# ESP-12E_Dev_Board_with_level_shifter.net
KiCad netlist of a schematic drawn in EAGLE
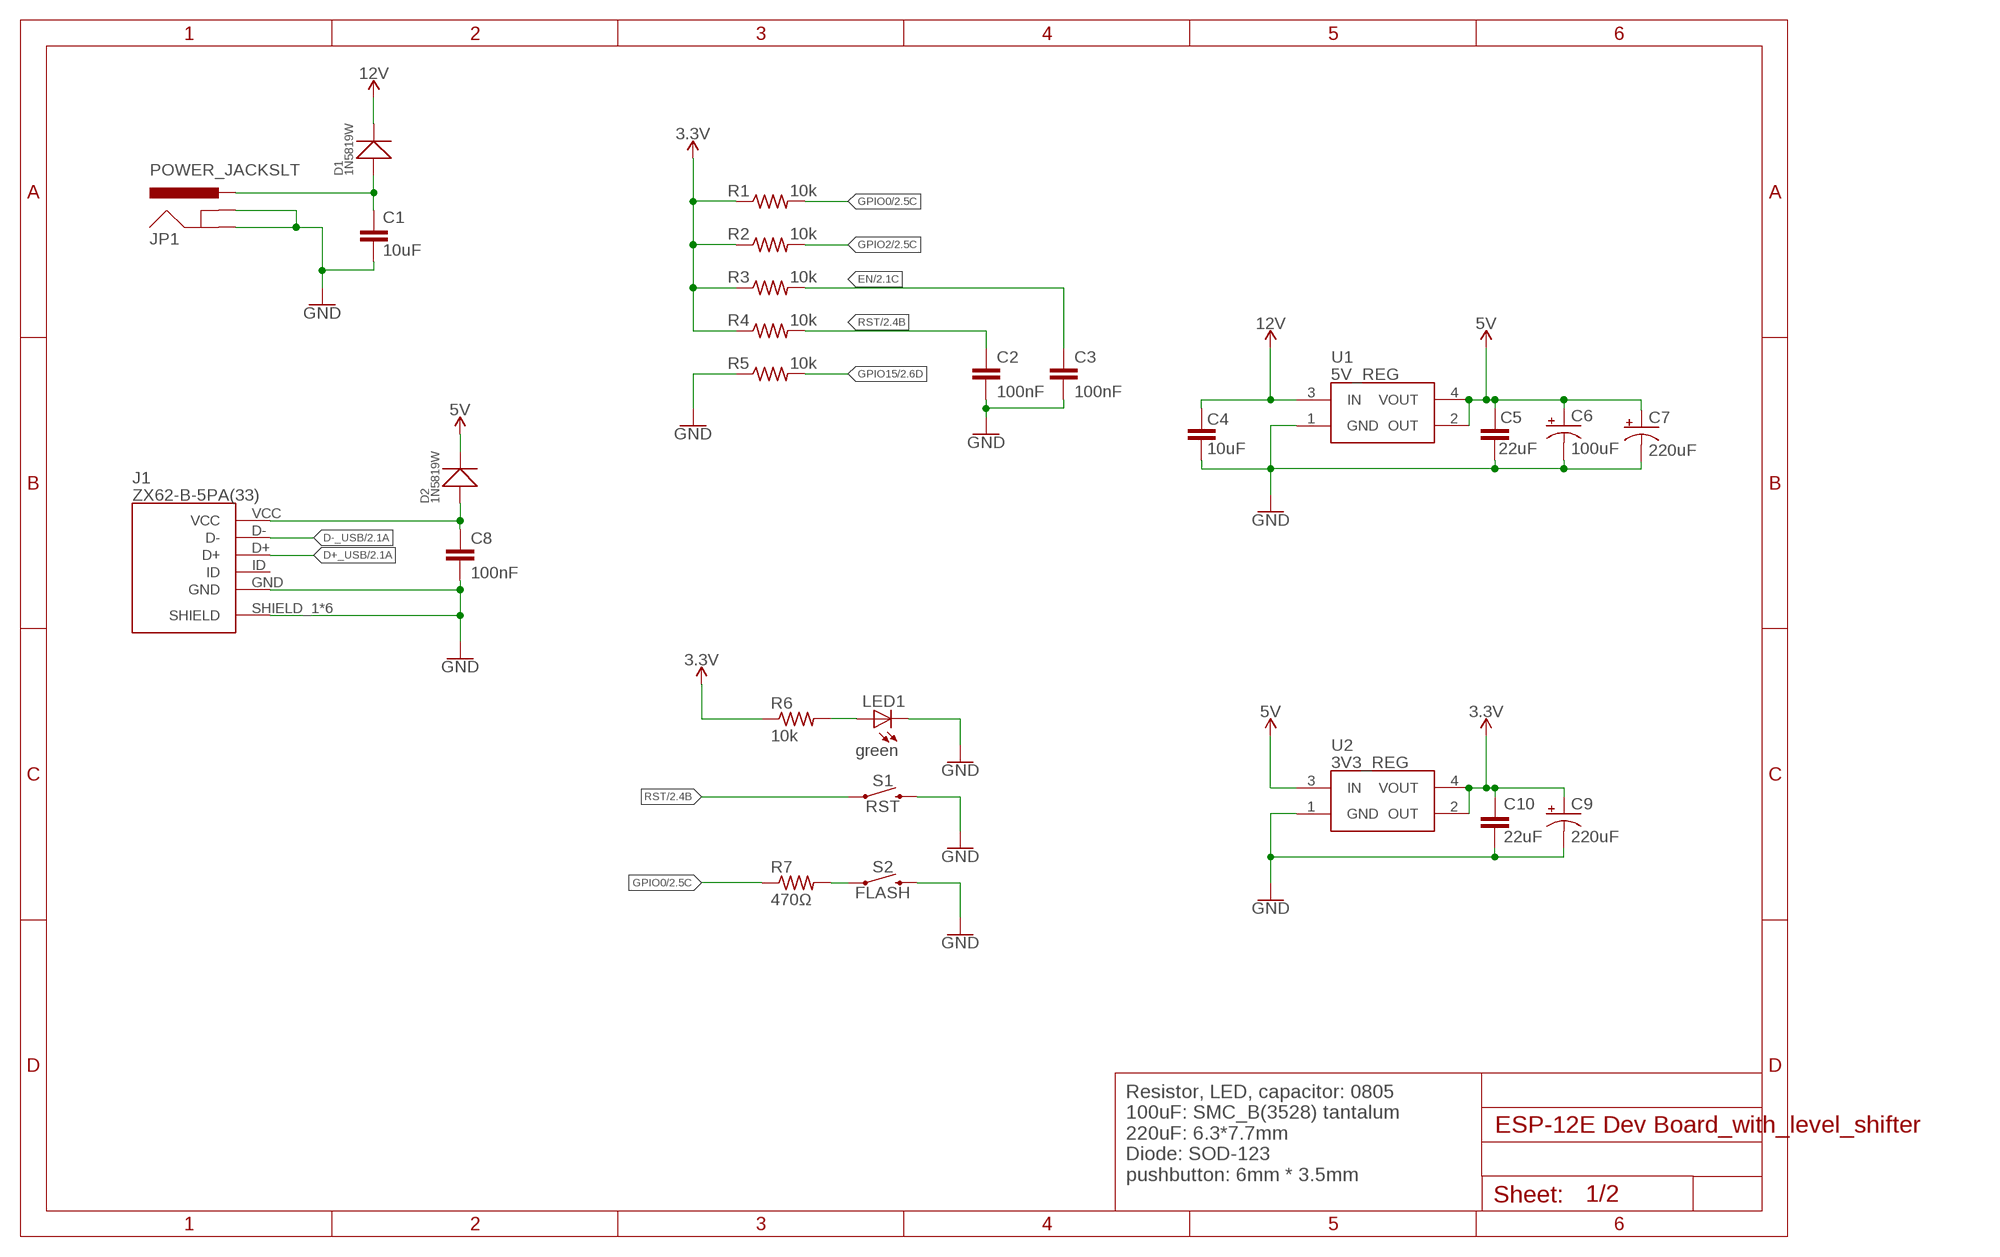
[diagram p0: schematic, sheet 1]
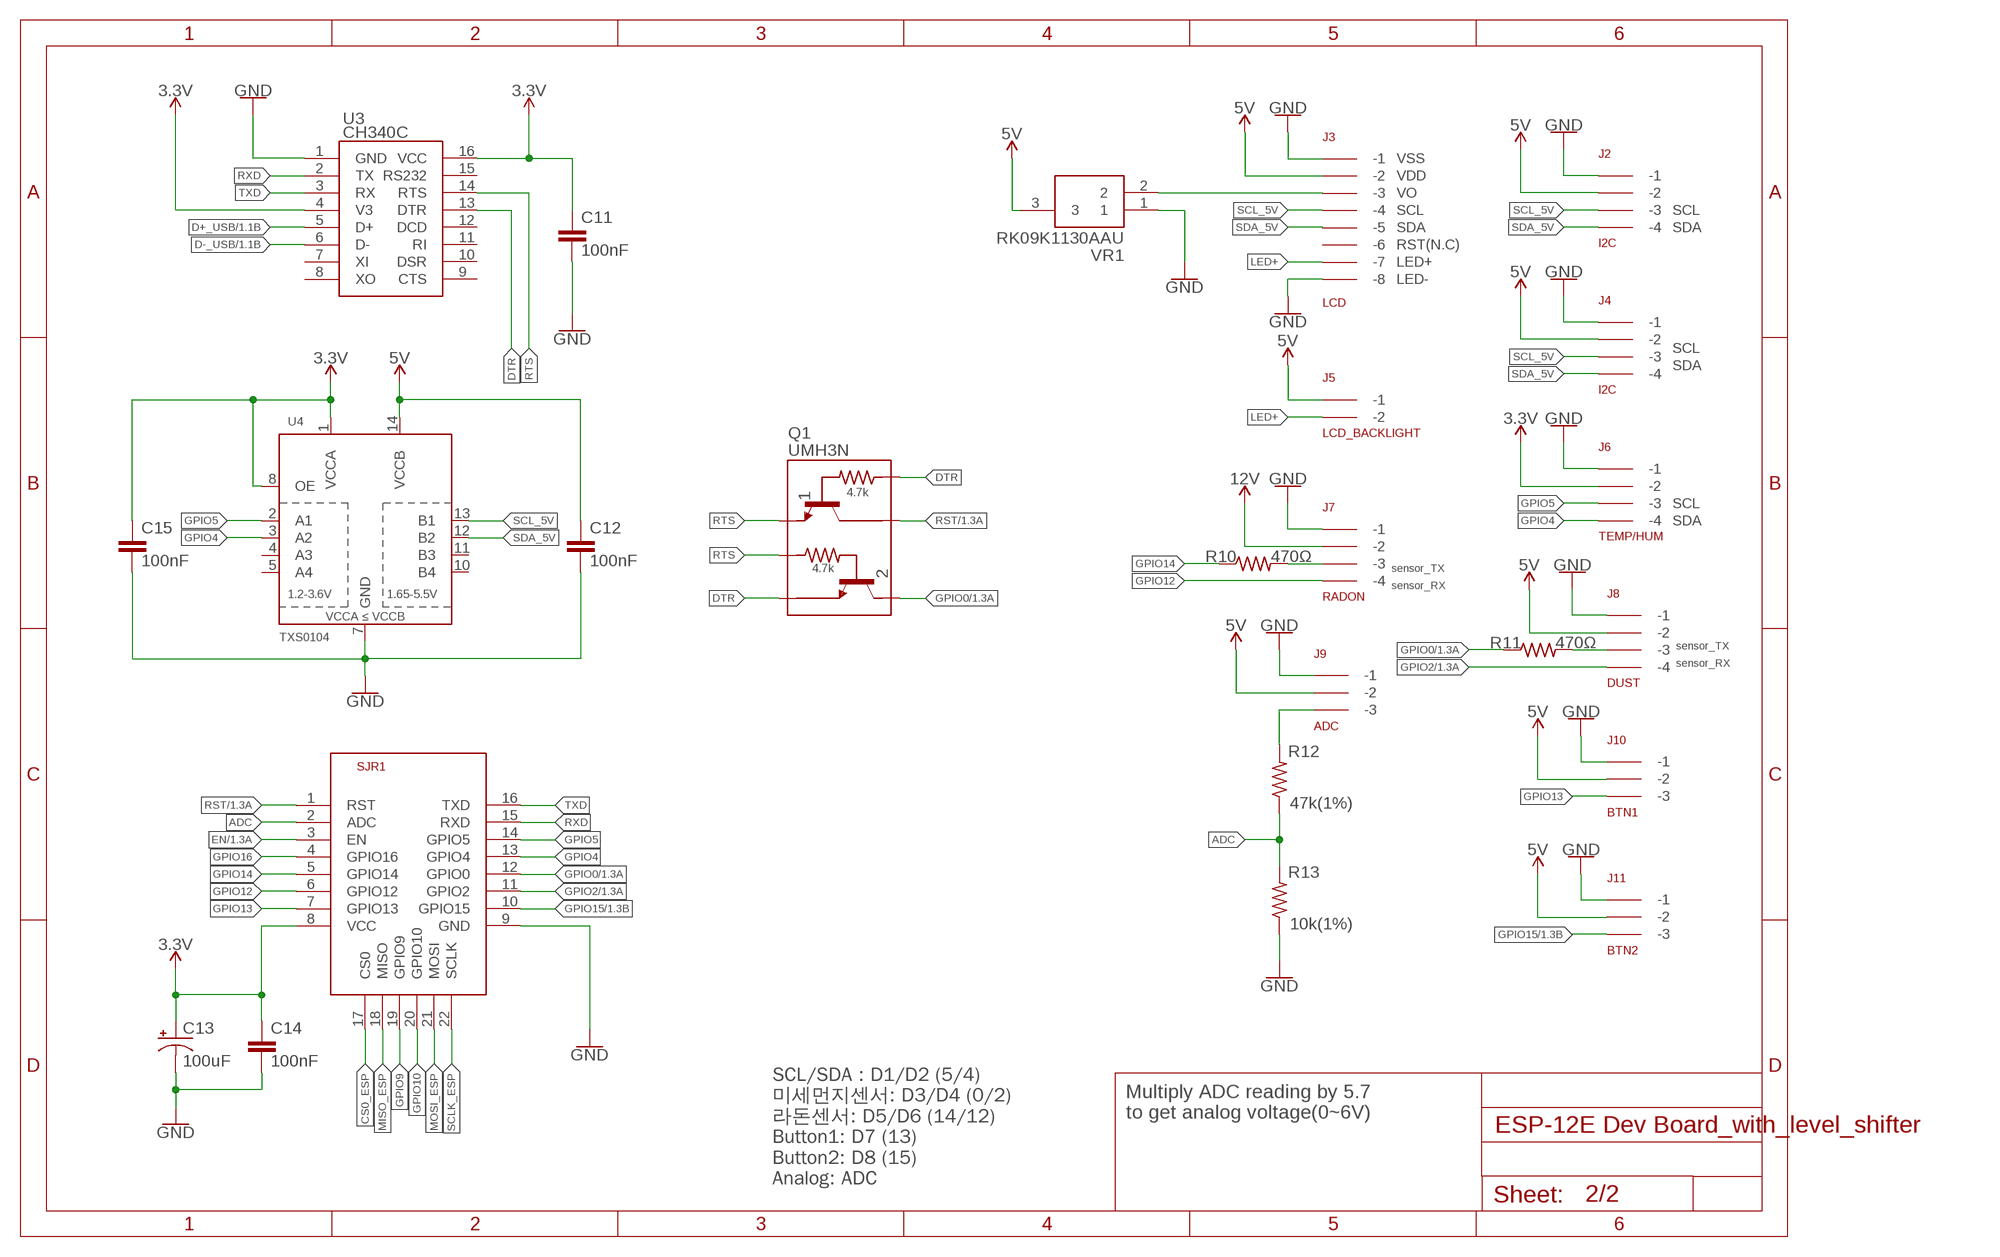
[diagram p1: schematic, sheet 2]

(export (version "E")
  (design (tool "Eeschema 10.0.6"))
  (components
    (comp (ref "C11")
      (value "100nF")
      (footprint "eagle-import:C0805")
      (libsource (lib "eagle-import") (part "C-EUC0805"))
    )
    (comp (ref "C12")
      (value "100nF")
      (footprint "eagle-import:C0805")
      (libsource (lib "eagle-import") (part "C-EUC0805"))
    )
    (comp (ref "C13")
      (value "100uF")
      (footprint "eagle-import:SMC_B")
      (libsource (lib "eagle-import") (part "CPOL-USSMCB"))
    )
    (comp (ref "C14")
      (value "100nF")
      (footprint "eagle-import:C0805")
      (libsource (lib "eagle-import") (part "C-EUC0805"))
    )
    (comp (ref "C15")
      (value "100nF")
      (footprint "eagle-import:C0805")
      (libsource (lib "eagle-import") (part "C-EUC0805"))
    )
    (comp (ref "J2")
      (value "I2C")
      (footprint "eagle-import:5267-4")
      (libsource (lib "eagle-import") (part "5267-4"))
    )
    (comp (ref "J3")
      (value "LCD")
      (footprint "eagle-import:5267-8")
      (libsource (lib "eagle-import") (part "5267-8"))
    )
    (comp (ref "J4")
      (value "I2C")
      (footprint "eagle-import:5267-4")
      (libsource (lib "eagle-import") (part "5267-4"))
    )
    (comp (ref "J5")
      (value "LCD_BACKLIGHT")
      (footprint "eagle-import:5267-2")
      (libsource (lib "eagle-import") (part "5267-2"))
    )
    (comp (ref "J6")
      (value "TEMP/HUM")
      (footprint "eagle-import:5267-4")
      (libsource (lib "eagle-import") (part "5267-4"))
    )
    (comp (ref "J7")
      (value "RADON")
      (footprint "eagle-import:5267-4")
      (libsource (lib "eagle-import") (part "5267-4"))
    )
    (comp (ref "J8")
      (value "DUST")
      (footprint "eagle-import:5267-4")
      (libsource (lib "eagle-import") (part "5267-4"))
    )
    (comp (ref "J9")
      (value "ADC")
      (footprint "eagle-import:5267-3")
      (libsource (lib "eagle-import") (part "5267-3"))
    )
    (comp (ref "J10")
      (value "BTN1")
      (footprint "eagle-import:5267-3")
      (libsource (lib "eagle-import") (part "5267-3"))
    )
    (comp (ref "J11")
      (value "BTN2")
      (footprint "eagle-import:5267-3")
      (libsource (lib "eagle-import") (part "5267-3"))
    )
    (comp (ref "Q1")
      (value "UMH3N")
      (footprint "eagle-import:SOT65P210X100-6N")
      (fields
        (field (name "MANUFACTURER_PART_NUMBER") "UMH3NFHATN")
        (field (name "MOUSER_PART_NUMBER") "755-UMH3NFHATN")
      )
      (libsource (lib "eagle-import") (part "UMH3NFHATN"))
    )
    (comp (ref "R10")
      (value "470Ω")
      (footprint "eagle-import:R0805")
      (libsource (lib "eagle-import") (part "R-US_R0805"))
    )
    (comp (ref "R11")
      (value "470Ω")
      (footprint "eagle-import:R0805")
      (libsource (lib "eagle-import") (part "R-US_R0805"))
    )
    (comp (ref "R12")
      (value "47k(1%)")
      (footprint "eagle-import:R0805")
      (libsource (lib "eagle-import") (part "R-US_R0805"))
    )
    (comp (ref "R13")
      (value "10k(1%)")
      (footprint "eagle-import:R0805")
      (libsource (lib "eagle-import") (part "R-US_R0805"))
    )
    (comp (ref "SJR1")
      (value "ESP-12E")
      (footprint "eagle-import:ESP8266-ESP12E")
      (libsource (lib "eagle-import") (part "ESP8266-12EESP12E"))
    )
    (comp (ref "U3")
      (value "CH340C")
      (footprint "eagle-import:SOIC16")
      (libsource (lib "eagle-import") (part "CH340G"))
    )
    (comp (ref "U4")
      (value "TXS0104")
      (footprint "eagle-import:TSSOP14")
      (libsource (lib "eagle-import") (part "TXB0104PWR"))
    )
    (comp (ref "VR1")
      (value "RK09K1130AAU")
      (footprint "eagle-import:RK09K1130BGM")
      (fields
        (field (name "MANUFACTURER_PART_NUMBER") "RK09K1130A6S")
        (field (name "MOUSER_PART_NUMBER") "688-RK09K1130A6S")
      )
      (libsource (lib "eagle-import") (part "RK09K1130A6S"))
    )
    (comp (ref "C1")
      (value "10uF")
      (footprint "eagle-import:C0805")
      (libsource (lib "eagle-import") (part "C-EUC0805"))
    )
    (comp (ref "C2")
      (value "100nF")
      (footprint "eagle-import:C0805")
      (libsource (lib "eagle-import") (part "C-EUC0805"))
    )
    (comp (ref "C3")
      (value "100nF")
      (footprint "eagle-import:C0805")
      (libsource (lib "eagle-import") (part "C-EUC0805"))
    )
    (comp (ref "C4")
      (value "10uF")
      (footprint "eagle-import:C0805")
      (libsource (lib "eagle-import") (part "C-EUC0805"))
    )
    (comp (ref "C5")
      (value "22uF")
      (footprint "eagle-import:C0805")
      (libsource (lib "eagle-import") (part "C-EUC0805"))
    )
    (comp (ref "C6")
      (value "100uF")
      (footprint "eagle-import:SMC_B")
      (libsource (lib "eagle-import") (part "CPOL-USSMCB"))
    )
    (comp (ref "C7")
      (value "220uF")
      (footprint "eagle-import:UD-6,3X7,7_NICHICON")
      (libsource (lib "eagle-import") (part "CPOL-USUD-6,3X7,7"))
    )
    (comp (ref "C8")
      (value "100nF")
      (footprint "eagle-import:C0805")
      (libsource (lib "eagle-import") (part "C-EUC0805"))
    )
    (comp (ref "C9")
      (value "220uF")
      (footprint "eagle-import:UD-6,3X7,7_NICHICON")
      (libsource (lib "eagle-import") (part "CPOL-USUD-6,3X7,7"))
    )
    (comp (ref "C10")
      (value "22uF")
      (footprint "eagle-import:C0805")
      (libsource (lib "eagle-import") (part "C-EUC0805"))
    )
    (comp (ref "D1")
      (value "1N5819W")
      (footprint "eagle-import:SOD-123")
      (fields (field (name "MPN") "SS0520-7-F"))
      (libsource (lib "eagle-import") (part "SMD-DIODE-SCHOTTKY-20V-500MA(SOD-123)"))
    )
    (comp (ref "D2")
      (value "1N5819W")
      (footprint "eagle-import:SOD-123")
      (fields (field (name "MPN") "SS0520-7-F"))
      (libsource (lib "eagle-import") (part "SMD-DIODE-SCHOTTKY-20V-500MA(SOD-123)"))
    )
    (comp (ref "J1")
      (value "ZX62-B-5PA(33)")
      (footprint "eagle-import:ZX62B5PA33")
      (fields (field (name "MOUSER_PART_NUMBER") "798-ZX62-B-5PA33"))
      (libsource (lib "eagle-import") (part "ZX62-B-5PA(33)"))
    )
    (comp (ref "JP1")
      (value "POWER_JACKSLT")
      (footprint "eagle-import:POWER_JACK_SLOT")
      (libsource (lib "eagle-import") (part "POWER_JACKSLT"))
    )
    (comp (ref "LED1")
      (value "green")
      (footprint "eagle-import:CHIP-LED0805")
      (libsource (lib "eagle-import") (part "LEDCHIP-LED0805"))
    )
    (comp (ref "R1")
      (value "10k")
      (footprint "eagle-import:R0805")
      (libsource (lib "eagle-import") (part "R-US_R0805"))
    )
    (comp (ref "R2")
      (value "10k")
      (footprint "eagle-import:R0805")
      (libsource (lib "eagle-import") (part "R-US_R0805"))
    )
    (comp (ref "R3")
      (value "10k")
      (footprint "eagle-import:R0805")
      (libsource (lib "eagle-import") (part "R-US_R0805"))
    )
    (comp (ref "R4")
      (value "10k")
      (footprint "eagle-import:R0805")
      (libsource (lib "eagle-import") (part "R-US_R0805"))
    )
    (comp (ref "R5")
      (value "10k")
      (footprint "eagle-import:R0805")
      (libsource (lib "eagle-import") (part "R-US_R0805"))
    )
    (comp (ref "R6")
      (value "10k")
      (footprint "eagle-import:R0805")
      (libsource (lib "eagle-import") (part "R-US_R0805"))
    )
    (comp (ref "R7")
      (value "470Ω")
      (footprint "eagle-import:R0805")
      (libsource (lib "eagle-import") (part "R-US_R0805"))
    )
    (comp (ref "S1")
      (value "RST")
      (footprint "eagle-import:TACTILE_SWITCH_SMD_6.0X3.5MM")
      (libsource (lib "eagle-import") (part "MOMENTARY-SWITCH-SPST-SMD-6.0X3.5MM"))
    )
    (comp (ref "S2")
      (value "FLASH")
      (footprint "eagle-import:TACTILE_SWITCH_SMD_6.0X3.5MM")
      (libsource (lib "eagle-import") (part "MOMENTARY-SWITCH-SPST-SMD-6.0X3.5MM"))
    )
    (comp (ref "U1")
      (value "5V_REG")
      (footprint "eagle-import:SOT230P700X170-4N")
      (fields
        (field (name "MANUFACTURER_PART_NUMBER") "AZ1117H-5.0TRE1")
        (field (name "MOUSER_PART_NUMBER") "621-AZ1117H-5.0TRE1")
      )
      (libsource (lib "eagle-import") (part "AZ1117H-5.0TRE1"))
    )
    (comp (ref "U2")
      (value "3V3_REG")
      (footprint "eagle-import:SOT230P700X170-4N")
      (fields
        (field (name "MANUFACTURER_PART_NUMBER") "AZ1117H-5.0TRE1")
        (field (name "MOUSER_PART_NUMBER") "621-AZ1117H-5.0TRE1")
      )
      (libsource (lib "eagle-import") (part "AZ1117H-5.0TRE1"))
    )
  )
  (nets
    (net (code "1") (name "3.3V") (class "Default")
      (node (ref "C10") (pin "2") (pinfunction "2_2") (pintype "passive"))
      (node (ref "C11") (pin "2") (pinfunction "2_2") (pintype "passive"))
      (node (ref "C13") (pin "+") (pinfunction "+_+") (pintype "passive"))
      (node (ref "C14") (pin "2") (pinfunction "2_2") (pintype "passive"))
      (node (ref "C15") (pin "2") (pinfunction "2_2") (pintype "passive"))
      (node (ref "C9") (pin "+") (pinfunction "+_+") (pintype "passive"))
      (node (ref "J6") (pin "P$2") (pinfunction "-2_P$2") (pintype "bidirectional"))
      (node (ref "R1") (pin "1") (pinfunction "1_1") (pintype "passive"))
      (node (ref "R2") (pin "1") (pinfunction "1_1") (pintype "passive"))
      (node (ref "R3") (pin "1") (pinfunction "1_1") (pintype "passive"))
      (node (ref "R4") (pin "1") (pinfunction "1_1") (pintype "passive"))
      (node (ref "R6") (pin "1") (pinfunction "1_1") (pintype "passive"))
      (node (ref "SJR1") (pin "8") (pinfunction "VCC_8") (pintype "bidirectional"))
      (node (ref "U2") (pin "2") (pinfunction "OUT_2") (pintype "bidirectional"))
      (node (ref "U2") (pin "4") (pinfunction "VOUT_4") (pintype "bidirectional"))
      (node (ref "U3") (pin "16") (pinfunction "VCC_16") (pintype "bidirectional"))
      (node (ref "U3") (pin "4") (pinfunction "V3_4") (pintype "bidirectional"))
      (node (ref "U4") (pin "1") (pinfunction "VCCA_1") (pintype "bidirectional"))
      (node (ref "U4") (pin "8") (pinfunction "OE_8") (pintype "bidirectional"))
    )
    (net (code "2") (name "5V") (class "Default")
      (node (ref "C12") (pin "2") (pinfunction "2_2") (pintype "passive"))
      (node (ref "C5") (pin "1") (pinfunction "1_1") (pintype "passive"))
      (node (ref "C6") (pin "+") (pinfunction "+_+") (pintype "passive"))
      (node (ref "C7") (pin "+") (pinfunction "+_+") (pintype "passive"))
      (node (ref "D2") (pin "-") (pinfunction "-_-") (pintype "passive"))
      (node (ref "J10") (pin "P$2") (pinfunction "-2_P$2") (pintype "bidirectional"))
      (node (ref "J11") (pin "P$2") (pinfunction "-2_P$2") (pintype "bidirectional"))
      (node (ref "J2") (pin "P$2") (pinfunction "-2_P$2") (pintype "bidirectional"))
      (node (ref "J3") (pin "P$2") (pinfunction "-2_P$2") (pintype "bidirectional"))
      (node (ref "J4") (pin "P$2") (pinfunction "-2_P$2") (pintype "bidirectional"))
      (node (ref "J5") (pin "P$1") (pinfunction "-1_P$1") (pintype "bidirectional"))
      (node (ref "J8") (pin "P$2") (pinfunction "-2_P$2") (pintype "bidirectional"))
      (node (ref "J9") (pin "P$2") (pinfunction "-2_P$2") (pintype "bidirectional"))
      (node (ref "U1") (pin "2") (pinfunction "OUT_2") (pintype "bidirectional"))
      (node (ref "U1") (pin "4") (pinfunction "VOUT_4") (pintype "bidirectional"))
      (node (ref "U2") (pin "3") (pinfunction "IN_3") (pintype "bidirectional"))
      (node (ref "U4") (pin "14") (pinfunction "VCCB_14") (pintype "bidirectional"))
      (node (ref "VR1") (pin "3") (pinfunction "3_3") (pintype "bidirectional"))
    )
    (net (code "3") (name "12V") (class "Default")
      (node (ref "C4") (pin "1") (pinfunction "1_1") (pintype "passive"))
      (node (ref "D1") (pin "-") (pinfunction "-_-") (pintype "passive"))
      (node (ref "J7") (pin "P$2") (pinfunction "-2_P$2") (pintype "bidirectional"))
      (node (ref "U1") (pin "3") (pinfunction "IN_3") (pintype "bidirectional"))
    )
    (net (code "4") (name "ADC") (class "Default")
      (node (ref "R12") (pin "1") (pinfunction "1_1") (pintype "passive"))
      (node (ref "R13") (pin "2") (pinfunction "2_2") (pintype "passive"))
      (node (ref "SJR1") (pin "2") (pinfunction "ADC_2") (pintype "bidirectional"))
    )
    (net (code "5") (name "CS0_ESP") (class "Default")
      (node (ref "SJR1") (pin "17") (pinfunction "CS0_17") (pintype "bidirectional"))
    )
    (net (code "6") (name "D+_USB") (class "Default")
      (node (ref "J1") (pin "D+") (pinfunction "D+_D+") (pintype "bidirectional"))
      (node (ref "U3") (pin "5") (pinfunction "D+_5") (pintype "bidirectional"))
    )
    (net (code "7") (name "D-_USB") (class "Default")
      (node (ref "J1") (pin "D-") (pinfunction "D-_D-") (pintype "bidirectional"))
      (node (ref "U3") (pin "6") (pinfunction "D-_6") (pintype "bidirectional"))
    )
    (net (code "8") (name "DTR") (class "Default")
      (node (ref "Q1") (pin "2") (pinfunction "2_2") (pintype "bidirectional"))
      (node (ref "Q1") (pin "4") (pinfunction "4_4") (pintype "bidirectional"))
      (node (ref "U3") (pin "13") (pinfunction "DTR_13") (pintype "bidirectional"))
    )
    (net (code "9") (name "EN") (class "Default")
      (node (ref "C3") (pin "2") (pinfunction "2_2") (pintype "passive"))
      (node (ref "R3") (pin "2") (pinfunction "2_2") (pintype "passive"))
      (node (ref "SJR1") (pin "3") (pinfunction "EN_3") (pintype "bidirectional"))
    )
    (net (code "10") (name "GND") (class "Default")
      (node (ref "C1") (pin "1") (pinfunction "1_1") (pintype "passive"))
      (node (ref "C10") (pin "1") (pinfunction "1_1") (pintype "passive"))
      (node (ref "C11") (pin "1") (pinfunction "1_1") (pintype "passive"))
      (node (ref "C12") (pin "1") (pinfunction "1_1") (pintype "passive"))
      (node (ref "C13") (pin "-") (pinfunction "-_-") (pintype "passive"))
      (node (ref "C14") (pin "1") (pinfunction "1_1") (pintype "passive"))
      (node (ref "C15") (pin "1") (pinfunction "1_1") (pintype "passive"))
      (node (ref "C2") (pin "1") (pinfunction "1_1") (pintype "passive"))
      (node (ref "C3") (pin "1") (pinfunction "1_1") (pintype "passive"))
      (node (ref "C4") (pin "2") (pinfunction "2_2") (pintype "passive"))
      (node (ref "C5") (pin "2") (pinfunction "2_2") (pintype "passive"))
      (node (ref "C6") (pin "-") (pinfunction "-_-") (pintype "passive"))
      (node (ref "C7") (pin "-") (pinfunction "-_-") (pintype "passive"))
      (node (ref "C8") (pin "1") (pinfunction "1_1") (pintype "passive"))
      (node (ref "C9") (pin "-") (pinfunction "-_-") (pintype "passive"))
      (node (ref "J1") (pin "GND") (pinfunction "GND_GND") (pintype "bidirectional"))
      (node (ref "J1") (pin "SHIELD_1") (pinfunction "SHIELD_SHIELD_1") (pintype "bidirectional"))
      (node (ref "J1") (pin "SHIELD_2") (pinfunction "SHIELD_SHIELD_2") (pintype "bidirectional"))
      (node (ref "J1") (pin "SHIELD_3") (pinfunction "SHIELD_SHIELD_3") (pintype "bidirectional"))
      (node (ref "J1") (pin "SHIELD_4") (pinfunction "SHIELD_SHIELD_4") (pintype "bidirectional"))
      (node (ref "J1") (pin "SHIELD_5") (pinfunction "SHIELD_SHIELD_5") (pintype "bidirectional"))
      (node (ref "J1") (pin "SHIELD_6") (pinfunction "SHIELD_SHIELD_6") (pintype "bidirectional"))
      (node (ref "J10") (pin "P$1") (pinfunction "-1_P$1") (pintype "bidirectional"))
      (node (ref "J11") (pin "P$1") (pinfunction "-1_P$1") (pintype "bidirectional"))
      (node (ref "J2") (pin "P$1") (pinfunction "-1_P$1") (pintype "bidirectional"))
      (node (ref "J3") (pin "P$1") (pinfunction "-1_P$1") (pintype "bidirectional"))
      (node (ref "J3") (pin "P$8") (pinfunction "-8_P$8") (pintype "bidirectional"))
      (node (ref "J4") (pin "P$1") (pinfunction "-1_P$1") (pintype "bidirectional"))
      (node (ref "J6") (pin "P$1") (pinfunction "-1_P$1") (pintype "bidirectional"))
      (node (ref "J7") (pin "P$1") (pinfunction "-1_P$1") (pintype "bidirectional"))
      (node (ref "J8") (pin "P$1") (pinfunction "-1_P$1") (pintype "bidirectional"))
      (node (ref "J9") (pin "P$1") (pinfunction "-1_P$1") (pintype "bidirectional"))
      (node (ref "JP1") (pin "GND@1") (pinfunction "GNDBREAK_GND@1") (pintype "power_in"))
      (node (ref "JP1") (pin "GND@2") (pinfunction "GND_GND@2") (pintype "power_in"))
      (node (ref "LED1") (pin "C") (pinfunction "C_C") (pintype "passive"))
      (node (ref "R13") (pin "1") (pinfunction "1_1") (pintype "passive"))
      (node (ref "R5") (pin "1") (pinfunction "1_1") (pintype "passive"))
      (node (ref "S1") (pin "2") (pinfunction "2_2") (pintype "passive"))
      (node (ref "S2") (pin "2") (pinfunction "2_2") (pintype "passive"))
      (node (ref "SJR1") (pin "9") (pinfunction "GND_9") (pintype "bidirectional"))
      (node (ref "U1") (pin "1") (pinfunction "GND_1") (pintype "bidirectional"))
      (node (ref "U2") (pin "1") (pinfunction "GND_1") (pintype "bidirectional"))
      (node (ref "U3") (pin "1") (pinfunction "GND_1") (pintype "bidirectional"))
      (node (ref "U4") (pin "7") (pinfunction "GND_7") (pintype "bidirectional"))
      (node (ref "VR1") (pin "1") (pinfunction "1_1") (pintype "bidirectional"))
    )
    (net (code "11") (name "GPIO0") (class "Default")
      (node (ref "Q1") (pin "3") (pinfunction "3_3") (pintype "bidirectional"))
      (node (ref "R1") (pin "2") (pinfunction "2_2") (pintype "passive"))
      (node (ref "R11") (pin "1") (pinfunction "1_1") (pintype "passive"))
      (node (ref "R7") (pin "1") (pinfunction "1_1") (pintype "passive"))
      (node (ref "SJR1") (pin "12") (pinfunction "GPIO0_12") (pintype "bidirectional"))
    )
    (net (code "12") (name "GPIO2") (class "Default")
      (node (ref "J8") (pin "P$4") (pinfunction "-4_P$4") (pintype "bidirectional"))
      (node (ref "R2") (pin "2") (pinfunction "2_2") (pintype "passive"))
      (node (ref "SJR1") (pin "11") (pinfunction "GPIO2_11") (pintype "bidirectional"))
    )
    (net (code "13") (name "GPIO4") (class "Default")
      (node (ref "J6") (pin "P$4") (pinfunction "-4_P$4") (pintype "bidirectional"))
      (node (ref "SJR1") (pin "13") (pinfunction "GPIO4_13") (pintype "bidirectional"))
      (node (ref "U4") (pin "3") (pinfunction "A2_3") (pintype "bidirectional"))
    )
    (net (code "14") (name "GPIO5") (class "Default")
      (node (ref "J6") (pin "P$3") (pinfunction "-3_P$3") (pintype "bidirectional"))
      (node (ref "SJR1") (pin "14") (pinfunction "GPIO5_14") (pintype "bidirectional"))
      (node (ref "U4") (pin "2") (pinfunction "A1_2") (pintype "bidirectional"))
    )
    (net (code "15") (name "GPIO9") (class "Default")
      (node (ref "SJR1") (pin "19") (pinfunction "GPIO9_19") (pintype "bidirectional"))
    )
    (net (code "16") (name "GPIO10") (class "Default")
      (node (ref "SJR1") (pin "20") (pinfunction "GPIO10_20") (pintype "bidirectional"))
    )
    (net (code "17") (name "GPIO12") (class "Default")
      (node (ref "J7") (pin "P$4") (pinfunction "-4_P$4") (pintype "bidirectional"))
      (node (ref "SJR1") (pin "6") (pinfunction "GPIO12_6") (pintype "bidirectional"))
    )
    (net (code "18") (name "GPIO13") (class "Default")
      (node (ref "J10") (pin "P$3") (pinfunction "-3_P$3") (pintype "bidirectional"))
      (node (ref "SJR1") (pin "7") (pinfunction "GPIO13_7") (pintype "bidirectional"))
    )
    (net (code "19") (name "GPIO14") (class "Default")
      (node (ref "R10") (pin "1") (pinfunction "1_1") (pintype "passive"))
      (node (ref "SJR1") (pin "5") (pinfunction "GPIO14_5") (pintype "bidirectional"))
    )
    (net (code "20") (name "GPIO15") (class "Default")
      (node (ref "J11") (pin "P$3") (pinfunction "-3_P$3") (pintype "bidirectional"))
      (node (ref "R5") (pin "2") (pinfunction "2_2") (pintype "passive"))
      (node (ref "SJR1") (pin "10") (pinfunction "GPIO15_10") (pintype "bidirectional"))
    )
    (net (code "21") (name "GPIO16") (class "Default")
      (node (ref "SJR1") (pin "4") (pinfunction "GPIO16_4") (pintype "bidirectional"))
    )
    (net (code "22") (name "LED+") (class "Default")
      (node (ref "J3") (pin "P$7") (pinfunction "-7_P$7") (pintype "bidirectional"))
      (node (ref "J5") (pin "P$2") (pinfunction "-2_P$2") (pintype "bidirectional"))
    )
    (net (code "23") (name "MISO_ESP") (class "Default")
      (node (ref "SJR1") (pin "18") (pinfunction "MISO_18") (pintype "bidirectional"))
    )
    (net (code "24") (name "MOSI_ESP") (class "Default")
      (node (ref "SJR1") (pin "21") (pinfunction "MOSI_21") (pintype "bidirectional"))
    )
    (net (code "25") (name "Net-(C1-Pad2)") (class "Default")
      (node (ref "C1") (pin "2") (pinfunction "2_2") (pintype "passive"))
      (node (ref "D1") (pin "+") (pinfunction "+_+") (pintype "passive"))
      (node (ref "JP1") (pin "PWR") (pinfunction "PWR_PWR") (pintype "power_in"))
    )
    (net (code "26") (name "Net-(C8-Pad2)") (class "Default")
      (node (ref "C8") (pin "2") (pinfunction "2_2") (pintype "passive"))
      (node (ref "D2") (pin "+") (pinfunction "+_+") (pintype "passive"))
      (node (ref "J1") (pin "VCC") (pinfunction "VCC_VCC") (pintype "bidirectional"))
    )
    (net (code "27") (name "Net-(J3--3)") (class "Default")
      (node (ref "J3") (pin "P$3") (pinfunction "-3_P$3") (pintype "bidirectional"))
      (node (ref "VR1") (pin "2") (pinfunction "2_2") (pintype "bidirectional"))
    )
    (net (code "28") (name "Net-(J7--3)") (class "Default")
      (node (ref "J7") (pin "P$3") (pinfunction "-3_P$3") (pintype "bidirectional"))
      (node (ref "R10") (pin "2") (pinfunction "2_2") (pintype "passive"))
    )
    (net (code "29") (name "Net-(J8--3)") (class "Default")
      (node (ref "J8") (pin "P$3") (pinfunction "-3_P$3") (pintype "bidirectional"))
      (node (ref "R11") (pin "2") (pinfunction "2_2") (pintype "passive"))
    )
    (net (code "30") (name "Net-(J9--3)") (class "Default")
      (node (ref "J9") (pin "P$3") (pinfunction "-3_P$3") (pintype "bidirectional"))
      (node (ref "R12") (pin "2") (pinfunction "2_2") (pintype "passive"))
    )
    (net (code "31") (name "Net-(LED1-PadA)") (class "Default")
      (node (ref "LED1") (pin "A") (pinfunction "A_A") (pintype "passive"))
      (node (ref "R6") (pin "2") (pinfunction "2_2") (pintype "passive"))
    )
    (net (code "32") (name "Net-(R7-Pad2)") (class "Default")
      (node (ref "R7") (pin "2") (pinfunction "2_2") (pintype "passive"))
      (node (ref "S2") (pin "1") (pinfunction "1_1") (pintype "passive"))
    )
    (net (code "33") (name "RST") (class "Default")
      (node (ref "C2") (pin "2") (pinfunction "2_2") (pintype "passive"))
      (node (ref "Q1") (pin "6") (pinfunction "6_6") (pintype "bidirectional"))
      (node (ref "R4") (pin "2") (pinfunction "2_2") (pintype "passive"))
      (node (ref "S1") (pin "1") (pinfunction "1_1") (pintype "passive"))
      (node (ref "SJR1") (pin "1") (pinfunction "RST_1") (pintype "bidirectional"))
    )
    (net (code "34") (name "RTS") (class "Default")
      (node (ref "Q1") (pin "1") (pinfunction "1_1") (pintype "bidirectional"))
      (node (ref "Q1") (pin "5") (pinfunction "5_5") (pintype "bidirectional"))
      (node (ref "U3") (pin "14") (pinfunction "RTS_14") (pintype "bidirectional"))
    )
    (net (code "35") (name "RXD") (class "Default")
      (node (ref "SJR1") (pin "15") (pinfunction "RXD_15") (pintype "bidirectional"))
      (node (ref "U3") (pin "2") (pinfunction "TX_2") (pintype "bidirectional"))
    )
    (net (code "36") (name "SCLK_ESP") (class "Default")
      (node (ref "SJR1") (pin "22") (pinfunction "SCLK_22") (pintype "bidirectional"))
    )
    (net (code "37") (name "SCL_5V") (class "Default")
      (node (ref "J2") (pin "P$3") (pinfunction "-3_P$3") (pintype "bidirectional"))
      (node (ref "J3") (pin "P$4") (pinfunction "-4_P$4") (pintype "bidirectional"))
      (node (ref "J4") (pin "P$3") (pinfunction "-3_P$3") (pintype "bidirectional"))
      (node (ref "U4") (pin "13") (pinfunction "B1_13") (pintype "bidirectional"))
    )
    (net (code "38") (name "SDA_5V") (class "Default")
      (node (ref "J2") (pin "P$4") (pinfunction "-4_P$4") (pintype "bidirectional"))
      (node (ref "J3") (pin "P$5") (pinfunction "-5_P$5") (pintype "bidirectional"))
      (node (ref "J4") (pin "P$4") (pinfunction "-4_P$4") (pintype "bidirectional"))
      (node (ref "U4") (pin "12") (pinfunction "B2_12") (pintype "bidirectional"))
    )
    (net (code "39") (name "TXD") (class "Default")
      (node (ref "SJR1") (pin "16") (pinfunction "TXD_16") (pintype "bidirectional"))
      (node (ref "U3") (pin "3") (pinfunction "RX_3") (pintype "bidirectional"))
    )
    (net (code "40") (name "unconnected-(J1-PadID)") (class "Default")
      (node (ref "J1") (pin "ID") (pinfunction "ID_ID") (pintype "bidirectional"))
    )
    (net (code "41") (name "unconnected-(J3--6-PadP$6)") (class "Default")
      (node (ref "J3") (pin "P$6") (pinfunction "-6_P$6") (pintype "bidirectional"))
    )
    (net (code "42") (name "unconnected-(U3-CTS-Pad9)") (class "Default")
      (node (ref "U3") (pin "9") (pinfunction "CTS_9") (pintype "bidirectional"))
    )
    (net (code "43") (name "unconnected-(U3-DCD-Pad12)") (class "Default")
      (node (ref "U3") (pin "12") (pinfunction "DCD_12") (pintype "bidirectional"))
    )
    (net (code "44") (name "unconnected-(U3-DSR-Pad10)") (class "Default")
      (node (ref "U3") (pin "10") (pinfunction "DSR_10") (pintype "bidirectional"))
    )
    (net (code "45") (name "unconnected-(U3-RI-Pad11)") (class "Default")
      (node (ref "U3") (pin "11") (pinfunction "RI_11") (pintype "bidirectional"))
    )
    (net (code "46") (name "unconnected-(U3-RS232-Pad15)") (class "Default")
      (node (ref "U3") (pin "15") (pinfunction "RS232_15") (pintype "bidirectional"))
    )
    (net (code "47") (name "unconnected-(U3-XI-Pad7)") (class "Default")
      (node (ref "U3") (pin "7") (pinfunction "XI_7") (pintype "bidirectional"))
    )
    (net (code "48") (name "unconnected-(U3-XO-Pad8)") (class "Default")
      (node (ref "U3") (pin "8") (pinfunction "XO_8") (pintype "bidirectional"))
    )
    (net (code "49") (name "unconnected-(U4-A3-Pad4)") (class "Default")
      (node (ref "U4") (pin "4") (pinfunction "A3_4") (pintype "bidirectional"))
    )
    (net (code "50") (name "unconnected-(U4-A4-Pad5)") (class "Default")
      (node (ref "U4") (pin "5") (pinfunction "A4_5") (pintype "bidirectional"))
    )
    (net (code "51") (name "unconnected-(U4-B3-Pad11)") (class "Default")
      (node (ref "U4") (pin "11") (pinfunction "B3_11") (pintype "bidirectional"))
    )
    (net (code "52") (name "unconnected-(U4-B4-Pad10)") (class "Default")
      (node (ref "U4") (pin "10") (pinfunction "B4_10") (pintype "bidirectional"))
    )
  )
)
